# Camera.net
KiCad netlist of a schematic drawn in Altium Designer
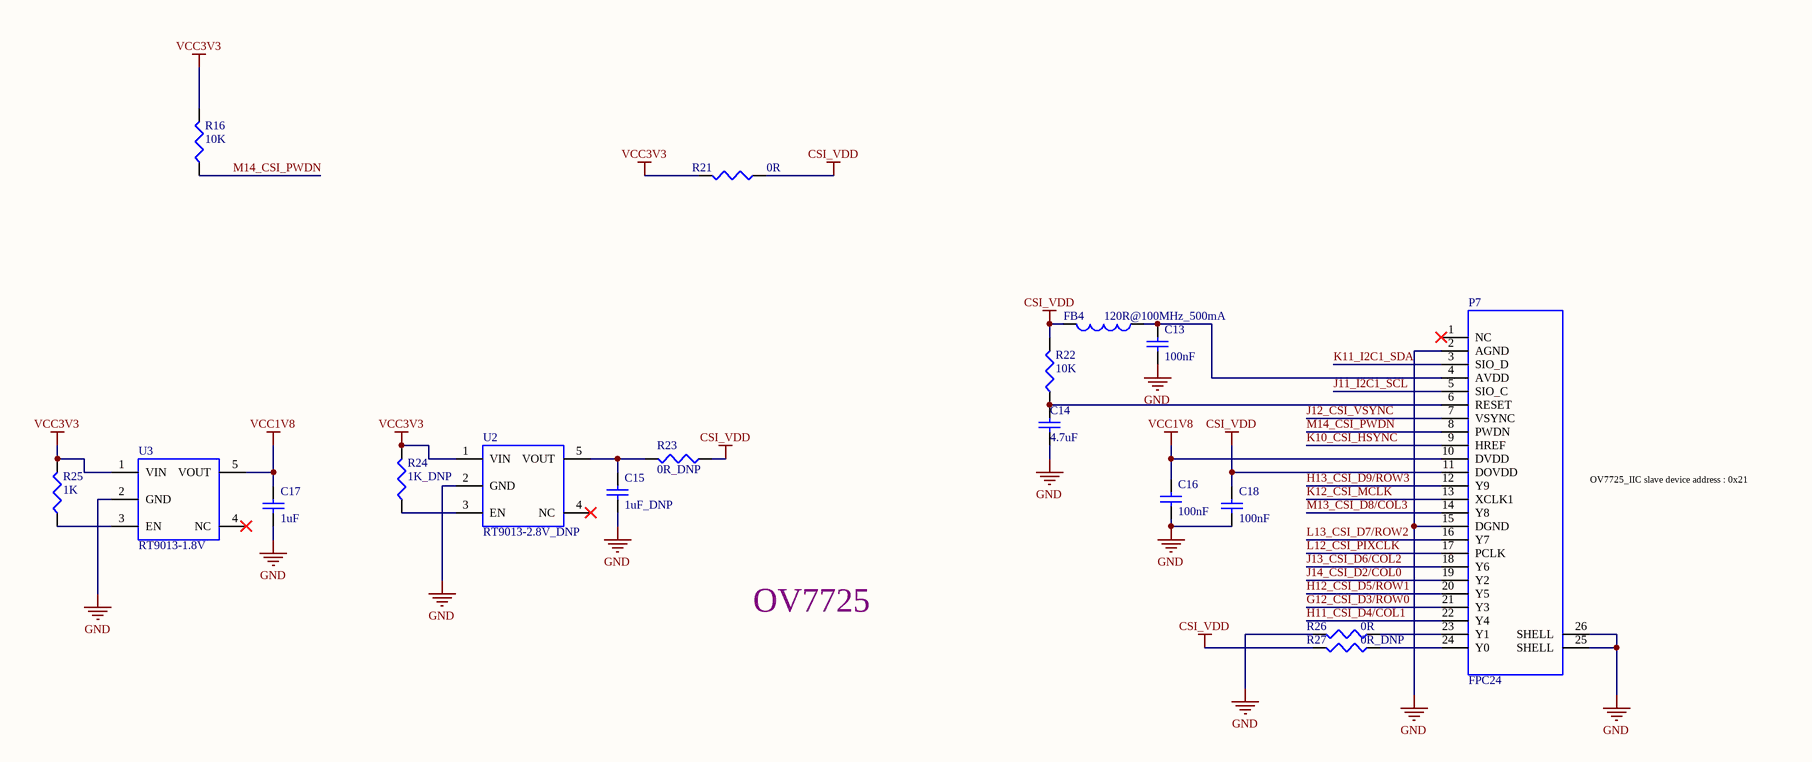
[diagram p0: Camera.SchDoc]

(export (version "E")
  (design (tool "Eeschema 10.0.6"))
  (components
    (comp (ref "C13")
      (value "100nF")
      (footprint "0603C+")
      (description "Capacitor")
      (fields (field (name "PUBLISHER") "Altium Limited"))
      (libsource (lib "Miscellaneous Devices") (part "Cap"))
    )
    (comp (ref "C14")
      (value "4.7uF")
      (footprint "0603C+")
      (description "Capacitor")
      (fields (field (name "Comment") "0.1uF") (field (name "PUBLISHER") "Altium Limited"))
      (libsource (lib "Miscellaneous Devices") (part "Cap"))
    )
    (comp (ref "C15")
      (value "1uF_DNP")
      (footprint "0603C+")
      (description "Capacitor")
      (fields (field (name "PUBLISHER") "Altium Limited"))
      (libsource (lib "Miscellaneous Devices") (part "Cap"))
    )
    (comp (ref "C16")
      (value "100nF")
      (footprint "0603C+")
      (description "Capacitor")
      (fields (field (name "Comment") "0.1uF") (field (name "PUBLISHER") "Altium Limited"))
      (libsource (lib "Miscellaneous Devices") (part "Cap"))
    )
    (comp (ref "C17")
      (value "1uF")
      (footprint "0603C+")
      (description "Capacitor")
      (fields (field (name "PUBLISHER") "Altium Limited"))
      (libsource (lib "Miscellaneous Devices") (part "Cap"))
    )
    (comp (ref "C18")
      (value "100nF")
      (footprint "0603C+")
      (description "Capacitor")
      (fields (field (name "PUBLISHER") "Altium Limited"))
      (libsource (lib "Miscellaneous Devices") (part "Cap"))
    )
    (comp (ref "FB4")
      (value "120R@100MHz_500mA")
      (footprint "0603R+")
      (description "Inductor")
      (fields (field (name "PUBLISHER") "Altium Limited"))
      (libsource (lib "Miscellaneous Devices") (part "Inductor"))
    )
    (comp (ref "P7") (value "FPC24") (footprint "FPC24") (libsource (lib "PCB_RT1052") (part "CON24")))
    (comp (ref "R16")
      (value "10K")
      (footprint "0603R+")
      (description "Resistor")
      (fields (field (name "PUBLISHER") "Altium Limited"))
      (libsource (lib "Miscellaneous Devices") (part "Res3"))
    )
    (comp (ref "R21")
      (value "0R")
      (footprint "0603R+")
      (description "Resistor")
      (fields (field (name "PUBLISHER") "Altium Limited"))
      (libsource (lib "Miscellaneous Devices") (part "Res3"))
    )
    (comp (ref "R22")
      (value "10K")
      (footprint "0603R+")
      (description "Resistor")
      (fields (field (name "PUBLISHER") "Altium Limited"))
      (libsource (lib "Miscellaneous Devices") (part "Res3"))
    )
    (comp (ref "R23")
      (value "0R_DNP")
      (footprint "0603R+")
      (description "Resistor")
      (fields (field (name "PUBLISHER") "Altium Limited"))
      (libsource (lib "Miscellaneous Devices") (part "Res3"))
    )
    (comp (ref "R24")
      (value "1K_DNP")
      (footprint "0603R+")
      (description "Resistor")
      (fields (field (name "PUBLISHER") "Altium Limited"))
      (libsource (lib "Miscellaneous Devices") (part "Res3"))
    )
    (comp (ref "R25")
      (value "1K")
      (footprint "0603R+")
      (description "Resistor")
      (fields (field (name "PUBLISHER") "Altium Limited"))
      (libsource (lib "Miscellaneous Devices") (part "Res3"))
    )
    (comp (ref "R26")
      (value "0R")
      (footprint "0603R+")
      (description "Resistor")
      (fields (field (name "PUBLISHER") "Altium Limited"))
      (libsource (lib "Miscellaneous Devices") (part "Res3"))
    )
    (comp (ref "R27")
      (value "0R_DNP")
      (footprint "0603R+")
      (description "Resistor")
      (fields (field (name "PUBLISHER") "Altium Limited"))
      (libsource (lib "Miscellaneous Devices") (part "Res3"))
    )
    (comp (ref "U2")
      (value "RT9013-2.8V_DNP")
      (footprint "SOT95P280X129-5N")
      (libsource (lib "IMX6QP-C") (part "RT9013"))
    )
    (comp (ref "U3")
      (value "RT9013-1.8V")
      (footprint "SOT95P280X129-5N")
      (libsource (lib "IMX6QP-C") (part "RT9013"))
    )
  )
  (nets
    (net (code "1") (name "/G12_CSI_D3{slash}ROW0") (class "Default")
      (node (ref "P7") (pin "21") (pinfunction "Y3_21") (pintype "passive"))
    )
    (net (code "2") (name "/H11_CSI_D4{slash}COL1") (class "Default")
      (node (ref "P7") (pin "22") (pinfunction "Y4_22") (pintype "passive"))
    )
    (net (code "3") (name "/H12_CSI_D5{slash}ROW1") (class "Default")
      (node (ref "P7") (pin "20") (pinfunction "Y5_20") (pintype "passive"))
    )
    (net (code "4") (name "/H13_CSI_D9{slash}ROW3") (class "Default")
      (node (ref "P7") (pin "12") (pinfunction "Y9_12") (pintype "passive"))
    )
    (net (code "5") (name "/J11_I2C1_SCL") (class "Default")
      (node (ref "P7") (pin "5") (pinfunction "SIO_C_5") (pintype "passive"))
    )
    (net (code "6") (name "/J12_CSI_VSYNC") (class "Default")
      (node (ref "P7") (pin "7") (pinfunction "VSYNC_7") (pintype "passive"))
    )
    (net (code "7") (name "/J13_CSI_D6{slash}COL2") (class "Default")
      (node (ref "P7") (pin "18") (pinfunction "Y6_18") (pintype "passive"))
    )
    (net (code "8") (name "/J14_CSI_D2{slash}COL0") (class "Default")
      (node (ref "P7") (pin "19") (pinfunction "Y2_19") (pintype "passive"))
    )
    (net (code "9") (name "/K10_CSI_HSYNC") (class "Default")
      (node (ref "P7") (pin "9") (pinfunction "HREF_9") (pintype "passive"))
    )
    (net (code "10") (name "/K11_I2C1_SDA") (class "Default")
      (node (ref "P7") (pin "3") (pinfunction "SIO_D_3") (pintype "passive"))
    )
    (net (code "11") (name "/K12_CSI_MCLK") (class "Default")
      (node (ref "P7") (pin "13") (pinfunction "XCLK1_13") (pintype "passive"))
    )
    (net (code "12") (name "/L12_CSI_PIXCLK") (class "Default")
      (node (ref "P7") (pin "17") (pinfunction "PCLK_17") (pintype "passive"))
    )
    (net (code "13") (name "/L13_CSI_D7{slash}ROW2") (class "Default")
      (node (ref "P7") (pin "16") (pinfunction "Y7_16") (pintype "passive"))
    )
    (net (code "14") (name "/M13_CSI_D8{slash}COL3") (class "Default")
      (node (ref "P7") (pin "14") (pinfunction "Y8_14") (pintype "passive"))
    )
    (net (code "15") (name "/M14_CSI_PWDN") (class "Default")
      (node (ref "P7") (pin "8") (pinfunction "PWDN_8") (pintype "passive"))
      (node (ref "R16") (pin "1") (pinfunction "1_1") (pintype "passive"))
    )
    (net (code "16") (name "CSI_VDD") (class "Default")
      (node (ref "C18") (pin "1") (pinfunction "1_1") (pintype "passive"))
      (node (ref "FB4") (pin "2") (pinfunction "2_2") (pintype "passive"))
      (node (ref "P7") (pin "11") (pinfunction "DOVDD_11") (pintype "passive"))
      (node (ref "R21") (pin "1") (pinfunction "1_1") (pintype "passive"))
      (node (ref "R22") (pin "2") (pinfunction "2_2") (pintype "passive"))
      (node (ref "R23") (pin "1") (pinfunction "1_1") (pintype "passive"))
      (node (ref "R27") (pin "2") (pinfunction "2_2") (pintype "passive"))
    )
    (net (code "17") (name "GND") (class "Default")
      (node (ref "C13") (pin "2") (pinfunction "2_2") (pintype "passive"))
      (node (ref "C14") (pin "2") (pinfunction "2_2") (pintype "passive"))
      (node (ref "C15") (pin "1") (pinfunction "1_1") (pintype "passive"))
      (node (ref "C16") (pin "2") (pinfunction "2_2") (pintype "passive"))
      (node (ref "C17") (pin "1") (pinfunction "1_1") (pintype "passive"))
      (node (ref "C18") (pin "2") (pinfunction "2_2") (pintype "passive"))
      (node (ref "P7") (pin "15") (pinfunction "DGND_15") (pintype "passive"))
      (node (ref "P7") (pin "2") (pinfunction "AGND_2") (pintype "passive"))
      (node (ref "P7") (pin "25") (pinfunction "SHELL_25") (pintype "passive"))
      (node (ref "P7") (pin "26") (pinfunction "SHELL_26") (pintype "passive"))
      (node (ref "R26") (pin "2") (pinfunction "2_2") (pintype "passive"))
      (node (ref "U2") (pin "2") (pinfunction "GND_2") (pintype "passive"))
      (node (ref "U3") (pin "2") (pinfunction "GND_2") (pintype "passive"))
    )
    (net (code "18") (name "Net-(P7-AVDD)") (class "Default")
      (node (ref "C13") (pin "1") (pinfunction "1_1") (pintype "passive"))
      (node (ref "FB4") (pin "1") (pinfunction "1_1") (pintype "passive"))
      (node (ref "P7") (pin "4") (pinfunction "AVDD_4") (pintype "passive"))
    )
    (net (code "19") (name "Net-(P7-RESET)") (class "Default")
      (node (ref "C14") (pin "1") (pinfunction "1_1") (pintype "passive"))
      (node (ref "P7") (pin "6") (pinfunction "RESET_6") (pintype "passive"))
      (node (ref "R22") (pin "1") (pinfunction "1_1") (pintype "passive"))
    )
    (net (code "20") (name "Net-(P7-Y0)") (class "Default")
      (node (ref "P7") (pin "24") (pinfunction "Y0_24") (pintype "passive"))
      (node (ref "R27") (pin "1") (pinfunction "1_1") (pintype "passive"))
    )
    (net (code "21") (name "Net-(P7-Y1)") (class "Default")
      (node (ref "P7") (pin "23") (pinfunction "Y1_23") (pintype "passive"))
      (node (ref "R26") (pin "1") (pinfunction "1_1") (pintype "passive"))
    )
    (net (code "22") (name "Net-(U2-EN)") (class "Default")
      (node (ref "R24") (pin "1") (pinfunction "1_1") (pintype "passive"))
      (node (ref "U2") (pin "3") (pinfunction "EN_3") (pintype "passive"))
    )
    (net (code "23") (name "Net-(U2-VOUT)") (class "Default")
      (node (ref "C15") (pin "2") (pinfunction "2_2") (pintype "passive"))
      (node (ref "R23") (pin "2") (pinfunction "2_2") (pintype "passive"))
      (node (ref "U2") (pin "5") (pinfunction "VOUT_5") (pintype "passive"))
    )
    (net (code "24") (name "Net-(U3-EN)") (class "Default")
      (node (ref "R25") (pin "1") (pinfunction "1_1") (pintype "passive"))
      (node (ref "U3") (pin "3") (pinfunction "EN_3") (pintype "passive"))
    )
    (net (code "25") (name "VCC1V8") (class "Default")
      (node (ref "C16") (pin "1") (pinfunction "1_1") (pintype "passive"))
      (node (ref "C17") (pin "2") (pinfunction "2_2") (pintype "passive"))
      (node (ref "P7") (pin "10") (pinfunction "DVDD_10") (pintype "passive"))
      (node (ref "U3") (pin "5") (pinfunction "VOUT_5") (pintype "passive"))
    )
    (net (code "26") (name "VCC3V3") (class "Default")
      (node (ref "R16") (pin "2") (pinfunction "2_2") (pintype "passive"))
      (node (ref "R21") (pin "2") (pinfunction "2_2") (pintype "passive"))
      (node (ref "R24") (pin "2") (pinfunction "2_2") (pintype "passive"))
      (node (ref "R25") (pin "2") (pinfunction "2_2") (pintype "passive"))
      (node (ref "U2") (pin "1") (pinfunction "VIN_1") (pintype "passive"))
      (node (ref "U3") (pin "1") (pinfunction "VIN_1") (pintype "passive"))
    )
    (net (code "27") (name "unconnected-(P7-NC-Pad1)") (class "Default")
      (node (ref "P7") (pin "1") (pinfunction "NC_1") (pintype "passive+no_connect"))
    )
    (net (code "28") (name "unconnected-(U2-NC-Pad4)") (class "Default")
      (node (ref "U2") (pin "4") (pinfunction "NC_4") (pintype "passive+no_connect"))
    )
    (net (code "29") (name "unconnected-(U3-NC-Pad4)") (class "Default")
      (node (ref "U3") (pin "4") (pinfunction "NC_4") (pintype "passive+no_connect"))
    )
  )
)
